# 3_power_controlled_sensors_schematics.net
KiCad netlist of a schematic drawn in EAGLE
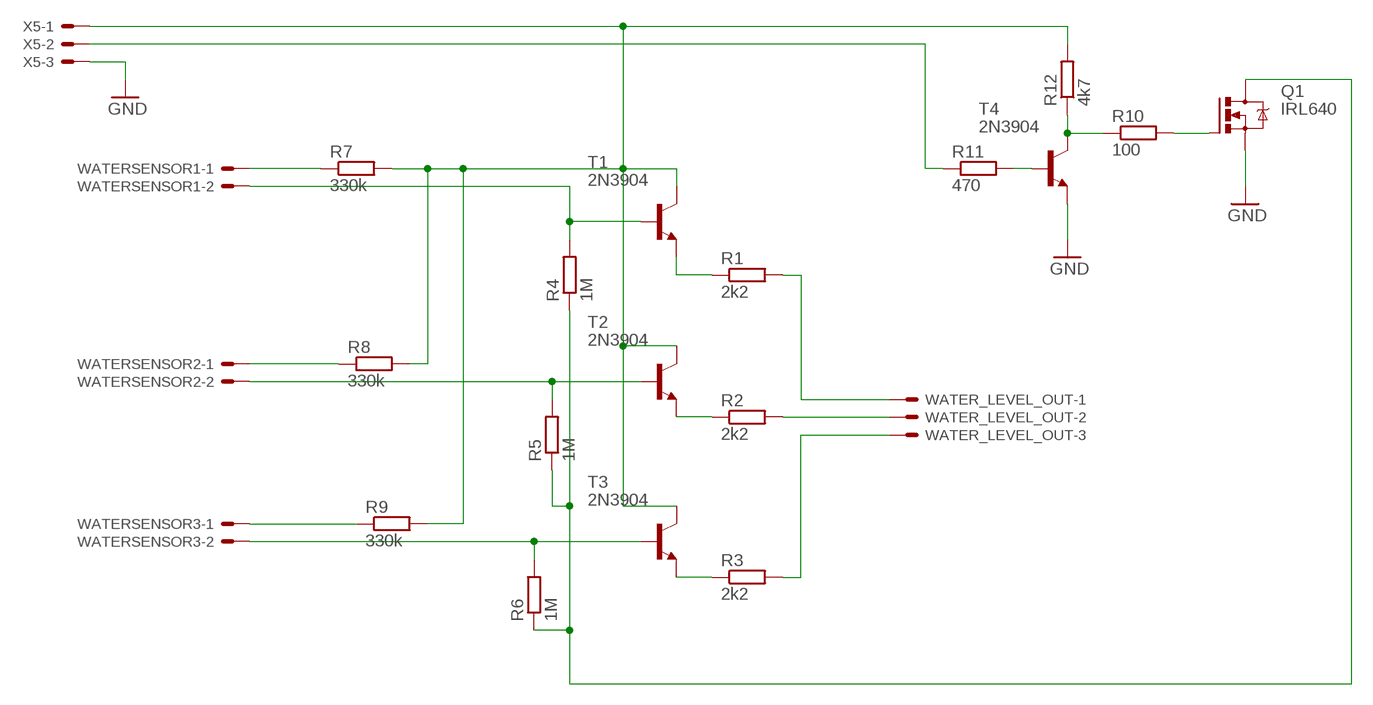
[diagram p0: schematic, sheet 1]

(export (version "E")
  (design (tool "Eeschema 10.0.6"))
  (components
    (comp (ref "Q1")
      (value "IRL640")
      (footprint "eagle-import:TO220BV")
      (libsource (lib "eagle-import") (part "IRF740"))
    )
    (comp (ref "R1")
      (value "2k2")
      (footprint "eagle-import:0207_7")
      (libsource (lib "eagle-import") (part "R-EU_0207/7"))
    )
    (comp (ref "R2")
      (value "2k2")
      (footprint "eagle-import:0207_7")
      (libsource (lib "eagle-import") (part "R-EU_0207/7"))
    )
    (comp (ref "R3")
      (value "2k2")
      (footprint "eagle-import:0207_7")
      (libsource (lib "eagle-import") (part "R-EU_0207/7"))
    )
    (comp (ref "R4")
      (value "1M")
      (footprint "eagle-import:0207_7")
      (libsource (lib "eagle-import") (part "R-EU_0207/7"))
    )
    (comp (ref "R5")
      (value "1M")
      (footprint "eagle-import:0207_7")
      (libsource (lib "eagle-import") (part "R-EU_0207/7"))
    )
    (comp (ref "R6")
      (value "1M")
      (footprint "eagle-import:0207_7")
      (libsource (lib "eagle-import") (part "R-EU_0207/7"))
    )
    (comp (ref "R7")
      (value "330k")
      (footprint "eagle-import:0207_7")
      (libsource (lib "eagle-import") (part "R-EU_0207/7"))
    )
    (comp (ref "R8")
      (value "330k")
      (footprint "eagle-import:0207_7")
      (libsource (lib "eagle-import") (part "R-EU_0207/7"))
    )
    (comp (ref "R9")
      (value "330k")
      (footprint "eagle-import:0207_7")
      (libsource (lib "eagle-import") (part "R-EU_0207/7"))
    )
    (comp (ref "R10")
      (value "100")
      (footprint "eagle-import:0207_7")
      (libsource (lib "eagle-import") (part "R-EU_0207/7"))
    )
    (comp (ref "R11")
      (value "470")
      (footprint "eagle-import:0207_7")
      (libsource (lib "eagle-import") (part "R-EU_0207/7"))
    )
    (comp (ref "R12")
      (value "4k7")
      (footprint "eagle-import:0207_7")
      (libsource (lib "eagle-import") (part "R-EU_0207/7"))
    )
    (comp (ref "T1")
      (value "2N3904")
      (footprint "eagle-import:TO92")
      (libsource (lib "eagle-import") (part "2N3904"))
    )
    (comp (ref "T2")
      (value "2N3904")
      (footprint "eagle-import:TO92")
      (libsource (lib "eagle-import") (part "2N3904"))
    )
    (comp (ref "T3")
      (value "2N3904")
      (footprint "eagle-import:TO92")
      (libsource (lib "eagle-import") (part "2N3904"))
    )
    (comp (ref "T4")
      (value "2N3904")
      (footprint "eagle-import:TO92")
      (libsource (lib "eagle-import") (part "2N3904"))
    )
    (comp (ref "WATERSENSOR1")
      (value "22-23-2021")
      (footprint "eagle-import:22-23-2021")
      (fields (field (name "MF") "MOLEX"))
      (libsource (lib "eagle-import") (part "22-23-2021"))
    )
    (comp (ref "WATERSENSOR2")
      (value "22-23-2021")
      (footprint "eagle-import:22-23-2021")
      (fields (field (name "MF") "MOLEX"))
      (libsource (lib "eagle-import") (part "22-23-2021"))
    )
    (comp (ref "WATERSENSOR3")
      (value "22-23-2021")
      (footprint "eagle-import:22-23-2021")
      (fields (field (name "MF") "MOLEX"))
      (libsource (lib "eagle-import") (part "22-23-2021"))
    )
    (comp (ref "WATER_LEVEL_OUT")
      (value "22-23-2031")
      (footprint "eagle-import:22-23-2031")
      (fields (field (name "MF") "MOLEX"))
      (libsource (lib "eagle-import") (part "22-23-2031"))
    )
    (comp (ref "X5")
      (value "22-23-2031")
      (footprint "eagle-import:22-23-2031")
      (fields (field (name "MF") "MOLEX"))
      (libsource (lib "eagle-import") (part "22-23-2031"))
    )
  )
  (nets
    (net (code "1") (name "GND") (class "Default")
      (node (ref "Q1") (pin "S") (pinfunction "S_S") (pintype "passive"))
      (node (ref "T4") (pin "3") (pinfunction "E_3") (pintype "passive"))
      (node (ref "X5") (pin "3") (pinfunction "S_3") (pintype "passive"))
    )
    (net (code "2") (name "Net-(Q1-PadD)") (class "Default")
      (node (ref "Q1") (pin "D") (pinfunction "D_D") (pintype "passive"))
      (node (ref "R4") (pin "1") (pinfunction "1_1") (pintype "passive"))
      (node (ref "R5") (pin "1") (pinfunction "1_1") (pintype "passive"))
      (node (ref "R6") (pin "1") (pinfunction "1_1") (pintype "passive"))
    )
    (net (code "3") (name "Net-(Q1-PadG)") (class "Default")
      (node (ref "Q1") (pin "G") (pinfunction "G_G") (pintype "passive"))
      (node (ref "R10") (pin "2") (pinfunction "2_2") (pintype "passive"))
    )
    (net (code "4") (name "Net-(T1-B)") (class "Default")
      (node (ref "R4") (pin "2") (pinfunction "2_2") (pintype "passive"))
      (node (ref "T1") (pin "2") (pinfunction "B_2") (pintype "passive"))
      (node (ref "WATERSENSOR1") (pin "2") (pinfunction "S_2") (pintype "passive"))
    )
    (net (code "5") (name "Net-(T1-C)") (class "Default")
      (node (ref "R12") (pin "2") (pinfunction "2_2") (pintype "passive"))
      (node (ref "R7") (pin "2") (pinfunction "2_2") (pintype "passive"))
      (node (ref "R8") (pin "2") (pinfunction "2_2") (pintype "passive"))
      (node (ref "R9") (pin "2") (pinfunction "2_2") (pintype "passive"))
      (node (ref "T1") (pin "1") (pinfunction "C_1") (pintype "passive"))
      (node (ref "T2") (pin "1") (pinfunction "C_1") (pintype "passive"))
      (node (ref "T3") (pin "1") (pinfunction "C_1") (pintype "passive"))
      (node (ref "X5") (pin "1") (pinfunction "S_1") (pintype "passive"))
    )
    (net (code "6") (name "Net-(T1-E)") (class "Default")
      (node (ref "R1") (pin "1") (pinfunction "1_1") (pintype "passive"))
      (node (ref "T1") (pin "3") (pinfunction "E_3") (pintype "passive"))
    )
    (net (code "7") (name "Net-(T2-B)") (class "Default")
      (node (ref "R5") (pin "2") (pinfunction "2_2") (pintype "passive"))
      (node (ref "T2") (pin "2") (pinfunction "B_2") (pintype "passive"))
      (node (ref "WATERSENSOR2") (pin "2") (pinfunction "S_2") (pintype "passive"))
    )
    (net (code "8") (name "Net-(T2-E)") (class "Default")
      (node (ref "R2") (pin "1") (pinfunction "1_1") (pintype "passive"))
      (node (ref "T2") (pin "3") (pinfunction "E_3") (pintype "passive"))
    )
    (net (code "9") (name "Net-(T3-B)") (class "Default")
      (node (ref "R6") (pin "2") (pinfunction "2_2") (pintype "passive"))
      (node (ref "T3") (pin "2") (pinfunction "B_2") (pintype "passive"))
      (node (ref "WATERSENSOR3") (pin "2") (pinfunction "S_2") (pintype "passive"))
    )
    (net (code "10") (name "Net-(T3-E)") (class "Default")
      (node (ref "R3") (pin "1") (pinfunction "1_1") (pintype "passive"))
      (node (ref "T3") (pin "3") (pinfunction "E_3") (pintype "passive"))
    )
    (net (code "11") (name "Net-(T4-B)") (class "Default")
      (node (ref "R11") (pin "2") (pinfunction "2_2") (pintype "passive"))
      (node (ref "T4") (pin "2") (pinfunction "B_2") (pintype "passive"))
    )
    (net (code "12") (name "Net-(T4-C)") (class "Default")
      (node (ref "R10") (pin "1") (pinfunction "1_1") (pintype "passive"))
      (node (ref "R12") (pin "1") (pinfunction "1_1") (pintype "passive"))
      (node (ref "T4") (pin "1") (pinfunction "C_1") (pintype "passive"))
    )
    (net (code "13") (name "Net-(WATERSENSOR1A-S)") (class "Default")
      (node (ref "R7") (pin "1") (pinfunction "1_1") (pintype "passive"))
      (node (ref "WATERSENSOR1") (pin "1") (pinfunction "S_1") (pintype "passive"))
    )
    (net (code "14") (name "Net-(WATERSENSOR2A-S)") (class "Default")
      (node (ref "R8") (pin "1") (pinfunction "1_1") (pintype "passive"))
      (node (ref "WATERSENSOR2") (pin "1") (pinfunction "S_1") (pintype "passive"))
    )
    (net (code "15") (name "Net-(WATERSENSOR3A-S)") (class "Default")
      (node (ref "R9") (pin "1") (pinfunction "1_1") (pintype "passive"))
      (node (ref "WATERSENSOR3") (pin "1") (pinfunction "S_1") (pintype "passive"))
    )
    (net (code "16") (name "Net-(WATER_LEVEL_OUTA-S)") (class "Default")
      (node (ref "R1") (pin "2") (pinfunction "2_2") (pintype "passive"))
      (node (ref "WATER_LEVEL_OUT") (pin "1") (pinfunction "S_1") (pintype "passive"))
    )
    (net (code "17") (name "Net-(WATER_LEVEL_OUTB-S)") (class "Default")
      (node (ref "R2") (pin "2") (pinfunction "2_2") (pintype "passive"))
      (node (ref "WATER_LEVEL_OUT") (pin "2") (pinfunction "S_2") (pintype "passive"))
    )
    (net (code "18") (name "Net-(WATER_LEVEL_OUTC-S)") (class "Default")
      (node (ref "R3") (pin "2") (pinfunction "2_2") (pintype "passive"))
      (node (ref "WATER_LEVEL_OUT") (pin "3") (pinfunction "S_3") (pintype "passive"))
    )
    (net (code "19") (name "Net-(X5B-S)") (class "Default")
      (node (ref "R11") (pin "1") (pinfunction "1_1") (pintype "passive"))
      (node (ref "X5") (pin "2") (pinfunction "S_2") (pintype "passive"))
    )
  )
)
